# BOT-CPU.net
KiCad netlist of a schematic drawn in Altium Designer
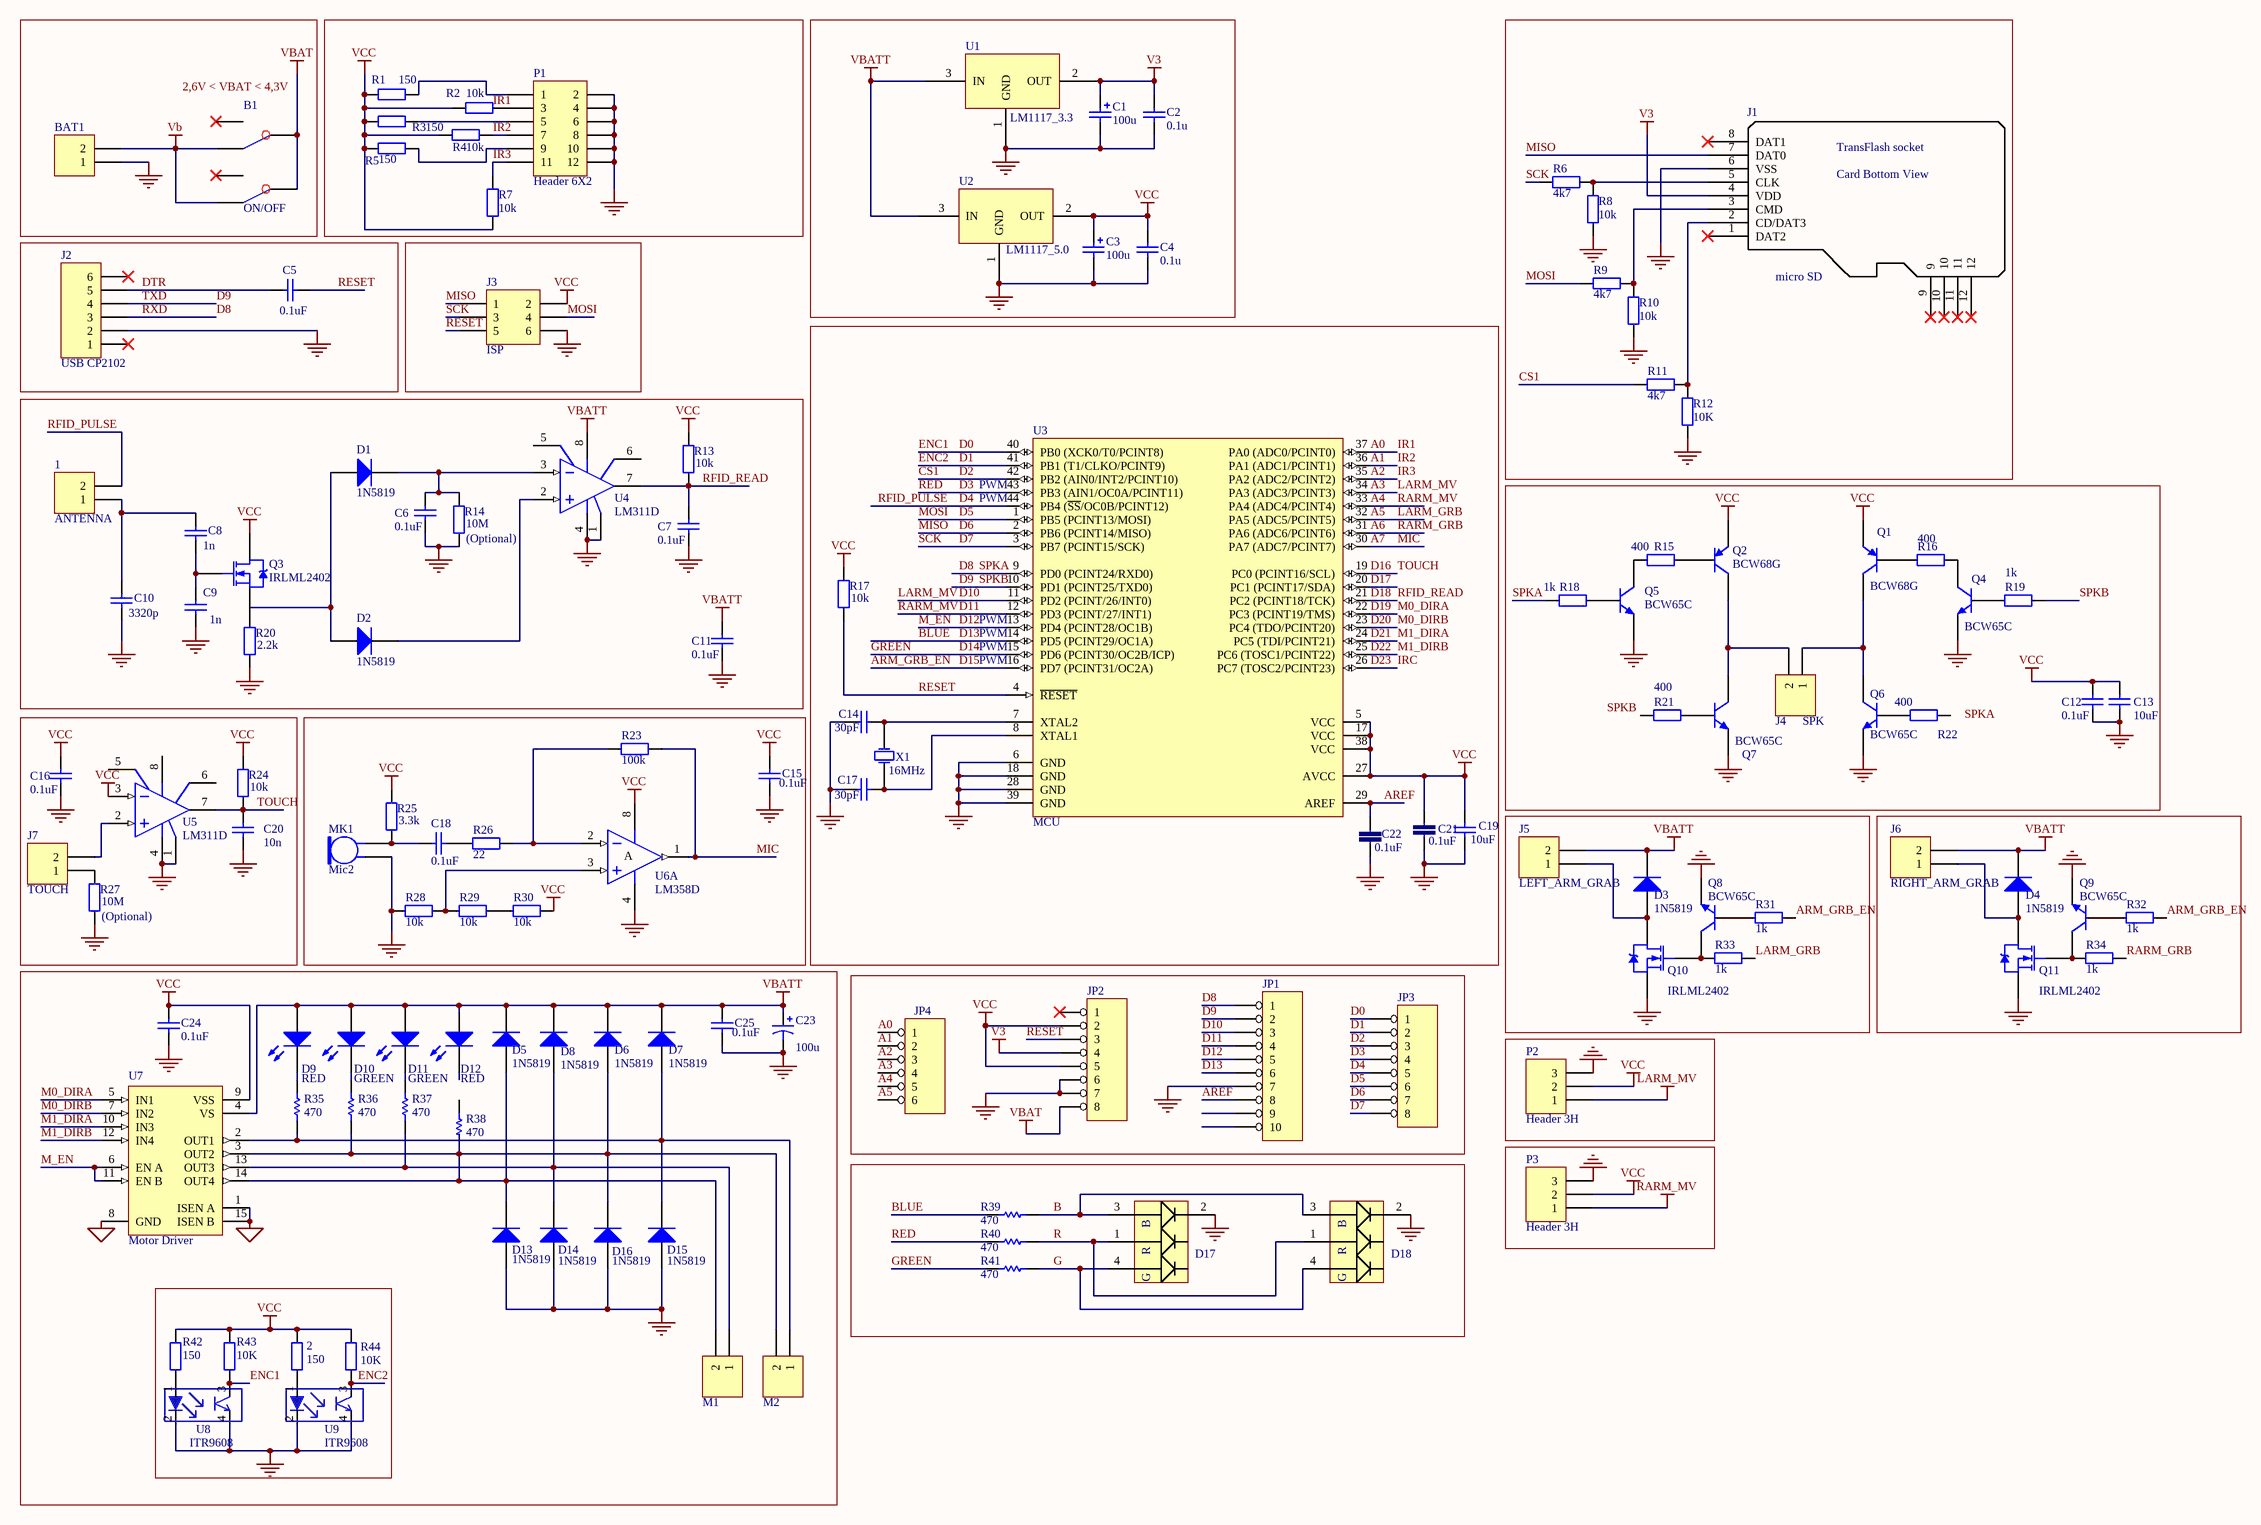
[diagram p0: BOT-CPU.SchDoc]

(export (version "E")
  (design (tool "Eeschema 10.0.6"))
  (components
    (comp (ref "1")
      (value "ANTENNA")
      (footprint "HDR1X2")
      (description "Header, 2-Pin")
      (fields (field (name "PUBLISHER") "Altium Limited"))
      (libsource (lib "") (part "Header 2_1"))
    )
    (comp (ref "2")
      (value "150")
      (footprint "0805")
      (description "Resistor")
      (fields (field (name "Comment") "1K") (field (name "PUBLISHER") "Altium Limited"))
      (libsource (lib "") (part "Res2_2"))
    )
    (comp (ref "B1") (value "ON/OFF") (footprint "KGPS22F03") (libsource (lib "*") (part "Component_1")))
    (comp (ref "BAT1")
      (value "Header 2")
      (footprint "CP2D2.54")
      (description "Header, 2-Pin")
      (fields (field (name "PUBLISHER") "Altium Limited"))
      (libsource (lib "") (part "Header 2_1"))
    )
    (comp (ref "C1")
      (value "100u")
      (footprint "C(D6.3*7)")
      (description "Polarized Capacitor (Axial)")
      (fields (field (name "ALTIUM_UNNAMED_1") "100u") (field (name "PUBLISHER") "Altium Limited"))
      (libsource (lib "*") (part "Cap Pol2"))
    )
    (comp (ref "C2")
      (value "0.1u")
      (footprint "0805")
      (description "Capacitor")
      (fields (field (name "PUBLISHER") "Altium Limited"))
      (libsource (lib "*") (part "Cap"))
    )
    (comp (ref "C3")
      (value "100u")
      (footprint "C(D6.3*7)")
      (description "Polarized Capacitor (Axial)")
      (fields (field (name "ALTIUM_UNNAMED_1") "100u") (field (name "PUBLISHER") "Altium Limited"))
      (libsource (lib "*") (part "Cap Pol2"))
    )
    (comp (ref "C4")
      (value "0.1u")
      (footprint "0805")
      (description "Capacitor")
      (fields (field (name "PUBLISHER") "Altium Limited"))
      (libsource (lib "*") (part "Cap"))
    )
    (comp (ref "C5")
      (value "0.1uF")
      (footprint "0805")
      (description "Capacitor")
      (fields (field (name "PUBLISHER") "*"))
      (libsource (lib "*") (part "Cap"))
    )
    (comp (ref "C6")
      (value "0.1uF")
      (footprint "0805")
      (description "Capacitor")
      (fields (field (name "PUBLISHER") "Altium Limited"))
      (libsource (lib "*") (part "Cap"))
    )
    (comp (ref "C7")
      (value "0.1uF")
      (footprint "0805")
      (description "Capacitor")
      (fields (field (name "PUBLISHER") "Altium Limited"))
      (libsource (lib "*") (part "Cap"))
    )
    (comp (ref "C8")
      (value "1n")
      (footprint "0805")
      (description "Capacitor")
      (fields (field (name "Comment") "1nF") (field (name "PUBLISHER") "Altium Limited"))
      (libsource (lib "*") (part "Cap"))
    )
    (comp (ref "C9")
      (value "1n")
      (footprint "0805")
      (description "Capacitor")
      (fields (field (name "Comment") "1nF") (field (name "PUBLISHER") "Altium Limited"))
      (libsource (lib "*") (part "Cap"))
    )
    (comp (ref "C10")
      (value "3320p")
      (footprint "0805")
      (description "Capacitor")
      (fields (field (name "Comment") "3320pF") (field (name "PUBLISHER") "Altium Limited"))
      (libsource (lib "*") (part "Cap"))
    )
    (comp (ref "C11")
      (value "0.1uF")
      (footprint "0805")
      (description "Capacitor")
      (fields (field (name "PUBLISHER") "Altium Limited"))
      (libsource (lib "*") (part "Cap"))
    )
    (comp (ref "C12")
      (value "0.1uF")
      (footprint "0805")
      (description "Capacitor")
      (fields (field (name "PUBLISHER") "Altium Limited"))
      (libsource (lib "*") (part "Cap"))
    )
    (comp (ref "C13")
      (value "10uF")
      (footprint "1206")
      (description "Capacitor")
      (fields (field (name "PUBLISHER") "Altium Limited"))
      (libsource (lib "*") (part "Cap"))
    )
    (comp (ref "C14")
      (value "30pF")
      (footprint "0805")
      (description "Capacitor")
      (fields (field (name "PUBLISHER") "Altium Limited"))
      (libsource (lib "*") (part "Cap"))
    )
    (comp (ref "C15")
      (value "0.1uF")
      (footprint "0805")
      (description "Capacitor")
      (fields (field (name "PUBLISHER") "Altium Limited"))
      (libsource (lib "*") (part "Cap"))
    )
    (comp (ref "C16")
      (value "0.1uF")
      (footprint "0805")
      (description "Capacitor")
      (fields (field (name "PUBLISHER") "Altium Limited"))
      (libsource (lib "*") (part "Cap"))
    )
    (comp (ref "C17")
      (value "30pF")
      (footprint "0805")
      (description "Capacitor")
      (fields (field (name "PUBLISHER") "Altium Limited"))
      (libsource (lib "*") (part "Cap"))
    )
    (comp (ref "C18")
      (value "0.1uF")
      (footprint "0805")
      (description "Capacitor")
      (fields (field (name "PUBLISHER") "Altium Limited"))
      (libsource (lib "") (part "Cap_1"))
    )
    (comp (ref "C19")
      (value "10uF")
      (footprint "1206")
      (description "Capacitor")
      (fields (field (name "PUBLISHER") "Altium Limited"))
      (libsource (lib "*") (part "Cap"))
    )
    (comp (ref "C20")
      (value "10n")
      (footprint "0805")
      (description "Capacitor")
      (fields (field (name "Comment") "0.1uF") (field (name "PUBLISHER") "Altium Limited"))
      (libsource (lib "*") (part "Cap"))
    )
    (comp (ref "C21") (value "0.1uF") (footprint "0805") (libsource (lib "*") (part "CAP0402")))
    (comp (ref "C22") (value "0.1uF") (footprint "0805") (libsource (lib "") (part "CAP0402_1")))
    (comp (ref "C23")
      (value "100u")
      (footprint "C(D6.3*7)")
      (description "Polarized Capacitor (Radial)")
      (fields (field (name "Comment") "220u") (field (name "PUBLISHER") "Altium Limited"))
      (libsource (lib "*") (part "Cap Pol1"))
    )
    (comp (ref "C24")
      (value "0.1uF")
      (footprint "0805")
      (description "Capacitor")
      (fields (field (name "PUBLISHER") "Altium Limited"))
      (libsource (lib "*") (part "Cap"))
    )
    (comp (ref "C25")
      (value "0.1uF")
      (footprint "0805")
      (description "Capacitor")
      (fields (field (name "PUBLISHER") "Altium Limited"))
      (libsource (lib "*") (part "Cap"))
    )
    (comp (ref "D1")
      (value "1N5819")
      (footprint "4007-smt")
      (description "Default Diode")
      (fields (field (name "PUBLISHER") "Altium Limited"))
      (libsource (lib "*") (part "Diode"))
    )
    (comp (ref "D2")
      (value "1N5819")
      (footprint "4007-smt")
      (description "Default Diode")
      (fields (field (name "PUBLISHER") "Altium Limited"))
      (libsource (lib "*") (part "Diode"))
    )
    (comp (ref "D3")
      (value "1N5819")
      (footprint "4007-smt")
      (description "Default Diode")
      (fields (field (name "PUBLISHER") "Altium Limited"))
      (libsource (lib "*") (part "Diode"))
    )
    (comp (ref "D4")
      (value "1N5819")
      (footprint "4007-smt")
      (description "Default Diode")
      (fields (field (name "PUBLISHER") "Altium Limited"))
      (libsource (lib "*") (part "Diode"))
    )
    (comp (ref "D5")
      (value "1N5819")
      (footprint "4007-smt")
      (description "Default Diode")
      (fields (field (name "PUBLISHER") "Altium Limited"))
      (libsource (lib "*") (part "Diode"))
    )
    (comp (ref "D6")
      (value "1N5819")
      (footprint "4007-smt")
      (description "Default Diode")
      (fields (field (name "PUBLISHER") "Altium Limited"))
      (libsource (lib "*") (part "Diode"))
    )
    (comp (ref "D7")
      (value "1N5819")
      (footprint "4007-smt")
      (description "Default Diode")
      (fields (field (name "PUBLISHER") "Altium Limited"))
      (libsource (lib "*") (part "Diode"))
    )
    (comp (ref "D8")
      (value "1N5819")
      (footprint "4007-smt")
      (description "Default Diode")
      (fields (field (name "PUBLISHER") "*"))
      (libsource (lib "*") (part "Diode"))
    )
    (comp (ref "D9")
      (value "RED")
      (footprint "LED-SMT")
      (description "Typical INFRARED GaAs LED")
      (fields (field (name "PUBLISHER") "Altium Limited"))
      (libsource (lib "*") (part "LED0"))
    )
    (comp (ref "D10")
      (value "GREEN")
      (footprint "LED-SMT")
      (description "Typical INFRARED GaAs LED")
      (fields (field (name "PUBLISHER") "Altium Limited"))
      (libsource (lib "*") (part "LED0"))
    )
    (comp (ref "D11")
      (value "GREEN")
      (footprint "LED-SMT")
      (description "Typical INFRARED GaAs LED")
      (fields (field (name "PUBLISHER") "Altium Limited"))
      (libsource (lib "*") (part "LED0"))
    )
    (comp (ref "D12")
      (value "RED")
      (footprint "LED-SMT")
      (description "Typical INFRARED GaAs LED")
      (fields (field (name "PUBLISHER") "Altium Limited"))
      (libsource (lib "*") (part "LED0"))
    )
    (comp (ref "D13")
      (value "1N5819")
      (footprint "4007-smt")
      (description "Default Diode")
      (fields (field (name "PUBLISHER") "Altium Limited"))
      (libsource (lib "*") (part "Diode"))
    )
    (comp (ref "D14")
      (value "1N5819")
      (footprint "4007-smt")
      (description "Default Diode")
      (fields (field (name "PUBLISHER") "Altium Limited"))
      (libsource (lib "*") (part "Diode"))
    )
    (comp (ref "D15")
      (value "1N5819")
      (footprint "4007-smt")
      (description "Default Diode")
      (fields (field (name "PUBLISHER") "Altium Limited"))
      (libsource (lib "*") (part "Diode"))
    )
    (comp (ref "D16")
      (value "1N5819")
      (footprint "4007-smt")
      (description "Default Diode")
      (fields (field (name "PUBLISHER") "Altium Limited"))
      (libsource (lib "*") (part "Diode"))
    )
    (comp (ref "D17") (value "RGB 5mm") (footprint "LED_RGB") (libsource (lib "*") (part "RGB PTH")))
    (comp (ref "D18") (value "RGB 5mm") (footprint "LED_RGB") (libsource (lib "*") (part "RGB PTH")))
    (comp (ref "J1")
      (value "micro SD")
      (footprint "MICRO_SD")
      (description "Transflash Socket")
      (libsource (lib "*") (part "JJ TRANSFLASH"))
    )
    (comp (ref "J2")
      (value "USB CP2102")
      (footprint "SIP6")
      (description "Header, 6-Pin")
      (fields (field (name "PUBLISHER") "Altium Limited"))
      (libsource (lib "*") (part "Header 6"))
    )
    (comp (ref "J3")
      (value "ISP")
      (footprint "con-6")
      (description "Header, 3-Pin, Dual row")
      (fields (field (name "PUBLISHER") "Altium Limited"))
      (libsource (lib "*") (part "Header 3X2"))
    )
    (comp (ref "J4")
      (value "SPK")
      (footprint "sip2")
      (description "Header, 2-Pin")
      (fields (field (name "PUBLISHER") "Altium Limited"))
      (libsource (lib "*") (part "Header 2"))
    )
    (comp (ref "J5")
      (value "LEFT_ARM_GRAB")
      (footprint "HDR1X2")
      (description "Header, 2-Pin")
      (fields (field (name "PUBLISHER") "Altium Limited"))
      (libsource (lib "") (part "Header 2_1"))
    )
    (comp (ref "J6")
      (value "RIGHT_ARM_GRAB")
      (footprint "HDR1X2")
      (description "Header, 2-Pin")
      (fields (field (name "PUBLISHER") "Altium Limited"))
      (libsource (lib "") (part "Header 2_1"))
    )
    (comp (ref "J7")
      (value "TOUCH")
      (footprint "HDR1X2")
      (description "Header, 2-Pin")
      (fields (field (name "PUBLISHER") "Altium Limited"))
      (libsource (lib "") (part "Header 2_1"))
    )
    (comp (ref "JP1") (value "PADS") (footprint "ARDUINO_10*1") (libsource (lib "*") (part "HEADER 10")))
    (comp (ref "JP2")
      (value "PADS")
      (footprint "ARDUINO_8*1")
      (description "8 Pin Header")
      (libsource (lib "*") (part "8 HEADER"))
    )
    (comp (ref "JP3")
      (value "PADS")
      (footprint "ARDUINO_8*1")
      (description "8 Pin Header")
      (libsource (lib "*") (part "8 HEADER"))
    )
    (comp (ref "JP4") (value "PADS") (footprint "ARDUINO_6*1") (libsource (lib "*") (part "HEADER 6")))
    (comp (ref "M1")
      (value "MOLEX")
      (footprint "CP2D2.54")
      (description "Header, 2-Pin")
      (fields (field (name "PUBLISHER") "Altium Limited"))
      (libsource (lib "*") (part "Header 2"))
    )
    (comp (ref "M2")
      (value "MOLEX")
      (footprint "CP2D2.54")
      (description "Header, 2-Pin")
      (fields (field (name "PUBLISHER") "Altium Limited"))
      (libsource (lib "*") (part "Header 2"))
    )
    (comp (ref "MK1")
      (value "Mic2")
      (footprint "MIC")
      (description "Microphone")
      (fields (field (name "PUBLISHER") "*"))
      (libsource (lib "*") (part "Mic2"))
    )
    (comp (ref "P1")
      (value "Header 6X2")
      (footprint "HDR2X6")
      (description "Header, 6-Pin, Dual row")
      (fields (field (name "PUBLISHER") "Altium Limited"))
      (libsource (lib "Miscellaneous Connectors") (part "Header 6X2"))
    )
    (comp (ref "P2")
      (value "Header 3H")
      (footprint "HDR1X3H")
      (description "Header, 3-Pin, Right Angle")
      (fields (field (name "PUBLISHER") "Altium Limited"))
      (libsource (lib "Miscellaneous Connectors") (part "Header 3H"))
    )
    (comp (ref "P3")
      (value "Header 3H")
      (footprint "HDR1X3H")
      (description "Header, 3-Pin, Right Angle")
      (fields (field (name "PUBLISHER") "Altium Limited"))
      (libsource (lib "Miscellaneous Connectors") (part "Header 3H"))
    )
    (comp (ref "Q1")
      (value "BCW68G")
      (footprint "SOT-23A_N")
      (description "PNP General Purpose Amplifier")
      (fields (field (name "PUBLISHER") "Altium Limited"))
      (libsource (lib "FSC Discrete BJT") (part "BCW68G"))
    )
    (comp (ref "Q2")
      (value "BCW68G")
      (footprint "SOT-23A_N")
      (description "PNP General Purpose Amplifier")
      (fields (field (name "PUBLISHER") "Altium Limited"))
      (libsource (lib "FSC Discrete BJT") (part "BCW68G"))
    )
    (comp (ref "Q3")
      (value "IRLML2402")
      (footprint "SOT-23_N")
      (description "HEXFET Power MOSFET")
      (fields (field (name "PUBLISHER") "Altium Limited"))
      (libsource (lib "IR Discrete MOSFET - Power") (part "IRLML2402"))
    )
    (comp (ref "Q4")
      (value "BCW65C")
      (footprint "SOT-23A_N")
      (description "NPN General Purpose Amplifier")
      (fields (field (name "PUBLISHER") "Altium Limited"))
      (libsource (lib "FSC Discrete BJT") (part "BCW65C"))
    )
    (comp (ref "Q5")
      (value "BCW65C")
      (footprint "SOT-23A_N")
      (description "NPN General Purpose Amplifier")
      (fields (field (name "PUBLISHER") "Altium Limited"))
      (libsource (lib "FSC Discrete BJT") (part "BCW65C"))
    )
    (comp (ref "Q6")
      (value "BCW65C")
      (footprint "SOT-23A_N")
      (description "NPN General Purpose Amplifier")
      (fields (field (name "PUBLISHER") "Altium Limited"))
      (libsource (lib "FSC Discrete BJT") (part "BCW65C"))
    )
    (comp (ref "Q7")
      (value "BCW65C")
      (footprint "SOT-23A_N")
      (description "NPN General Purpose Amplifier")
      (fields (field (name "PUBLISHER") "Altium Limited"))
      (libsource (lib "FSC Discrete BJT") (part "BCW65C"))
    )
    (comp (ref "Q8")
      (value "BCW65C")
      (footprint "SOT-23A_N")
      (description "NPN General Purpose Amplifier")
      (fields (field (name "PUBLISHER") "Altium Limited"))
      (libsource (lib "FSC Discrete BJT") (part "BCW65C"))
    )
    (comp (ref "Q9")
      (value "BCW65C")
      (footprint "SOT-23A_N")
      (description "NPN General Purpose Amplifier")
      (fields (field (name "PUBLISHER") "Altium Limited"))
      (libsource (lib "FSC Discrete BJT") (part "BCW65C"))
    )
    (comp (ref "Q10")
      (value "IRLML2402")
      (footprint "SOT-23_N")
      (description "HEXFET Power MOSFET")
      (fields (field (name "PUBLISHER") "Altium Limited"))
      (libsource (lib "IR Discrete MOSFET - Power") (part "IRLML2402"))
    )
    (comp (ref "Q11")
      (value "IRLML2402")
      (footprint "SOT-23_N")
      (description "HEXFET Power MOSFET")
      (fields (field (name "PUBLISHER") "Altium Limited"))
      (libsource (lib "IR Discrete MOSFET - Power") (part "IRLML2402"))
    )
    (comp (ref "R1")
      (value "150")
      (footprint "0805")
      (description "Resistor")
      (fields (field (name "PUBLISHER") "Altium Limited"))
      (libsource (lib "*") (part "Res2"))
    )
    (comp (ref "R2")
      (value "10k")
      (footprint "0805")
      (description "Resistor")
      (fields (field (name "PUBLISHER") "Altium Limited"))
      (libsource (lib "*") (part "Res2"))
    )
    (comp (ref "R3")
      (value "150")
      (footprint "0805")
      (description "Resistor")
      (fields (field (name "PUBLISHER") "Altium Limited"))
      (libsource (lib "*") (part "Res2"))
    )
    (comp (ref "R4")
      (value "10k")
      (footprint "0805")
      (description "Resistor")
      (fields (field (name "PUBLISHER") "Altium Limited"))
      (libsource (lib "*") (part "Res2"))
    )
    (comp (ref "R5")
      (value "150")
      (footprint "0805")
      (description "Resistor")
      (fields (field (name "PUBLISHER") "Altium Limited"))
      (libsource (lib "*") (part "Res2"))
    )
    (comp (ref "R6")
      (value "4k7")
      (footprint "0805")
      (description "Resistor")
      (fields (field (name "PUBLISHER") "Altium Limited"))
      (libsource (lib "") (part "Res2_1"))
    )
    (comp (ref "R7")
      (value "10k")
      (footprint "0805")
      (description "Resistor")
      (fields (field (name "PUBLISHER") "Altium Limited"))
      (libsource (lib "") (part "Res2_2"))
    )
    (comp (ref "R8")
      (value "10k")
      (footprint "0805")
      (description "Resistor")
      (fields (field (name "PUBLISHER") "Altium Limited"))
      (libsource (lib "") (part "Res2_3"))
    )
    (comp (ref "R9")
      (value "4k7")
      (footprint "0805")
      (description "Resistor")
      (fields (field (name "Comment") "10k") (field (name "PUBLISHER") "Altium Limited"))
      (libsource (lib "") (part "Res2_1"))
    )
    (comp (ref "R10")
      (value "10k")
      (footprint "0805")
      (description "Resistor")
      (fields (field (name "Comment") "20K") (field (name "PUBLISHER") "Altium Limited"))
      (libsource (lib "") (part "Res2_3"))
    )
    (comp (ref "R11")
      (value "4k7")
      (footprint "0805")
      (description "Resistor")
      (fields (field (name "Comment") "10k") (field (name "PUBLISHER") "Altium Limited"))
      (libsource (lib "") (part "Res2_3"))
    )
    (comp (ref "R12")
      (value "10K")
      (footprint "0805")
      (description "Resistor")
      (fields (field (name "PUBLISHER") "Altium Limited"))
      (libsource (lib "") (part "Res2_1"))
    )
    (comp (ref "R13")
      (value "10k")
      (footprint "0805")
      (description "Resistor")
      (fields (field (name "PUBLISHER") "Altium Limited"))
      (libsource (lib "") (part "Res2_1"))
    )
    (comp (ref "R14")
      (value "(Optional)")
      (footprint "0805")
      (description "Resistor")
      (fields (field (name "ALTIUM_VALUE") "10M") (field (name "PUBLISHER") "Altium Limited"))
      (libsource (lib "") (part "Res2_1"))
    )
    (comp (ref "R15")
      (value "400")
      (footprint "0805")
      (description "Resistor")
      (fields (field (name "PUBLISHER") "Altium Limited"))
      (libsource (lib "*") (part "Res2"))
    )
    (comp (ref "R16")
      (value "400")
      (footprint "0805")
      (description "Resistor")
      (fields (field (name "PUBLISHER") "Altium Limited"))
      (libsource (lib "") (part "Res2_1"))
    )
    (comp (ref "R17")
      (value "10k")
      (footprint "0805")
      (description "Resistor")
      (fields (field (name "Comment") "2.2k") (field (name "PUBLISHER") "Altium Limited"))
      (libsource (lib "") (part "Res2_1"))
    )
    (comp (ref "R18")
      (value "1k")
      (footprint "0805")
      (description "Resistor")
      (fields (field (name "Comment") "1K") (field (name "PUBLISHER") "Altium Limited"))
      (libsource (lib "*") (part "Res2"))
    )
    (comp (ref "R19")
      (value "1k")
      (footprint "0805")
      (description "Resistor")
      (fields (field (name "Comment") "1K") (field (name "PUBLISHER") "Altium Limited"))
      (libsource (lib "") (part "Res2_1"))
    )
    (comp (ref "R20")
      (value "2.2k")
      (footprint "0805")
      (description "Resistor")
      (fields (field (name "PUBLISHER") "Altium Limited"))
      (libsource (lib "") (part "Res2_1"))
    )
    (comp (ref "R21")
      (value "400")
      (footprint "0805")
      (description "Resistor")
      (fields (field (name "PUBLISHER") "Altium Limited"))
      (libsource (lib "*") (part "Res2"))
    )
    (comp (ref "R22")
      (value "400")
      (footprint "0805")
      (description "Resistor")
      (fields (field (name "PUBLISHER") "Altium Limited"))
      (libsource (lib "") (part "Res2_1"))
    )
    (comp (ref "R23")
      (value "100k")
      (footprint "0805")
      (description "Resistor")
      (fields (field (name "Comment") "1M") (field (name "PUBLISHER") "Altium Limited"))
      (libsource (lib "*") (part "Res2"))
    )
    (comp (ref "R24")
      (value "10k")
      (footprint "0805")
      (description "Resistor")
      (fields (field (name "PUBLISHER") "Altium Limited"))
      (libsource (lib "") (part "Res2_1"))
    )
    (comp (ref "R25")
      (value "3.3k")
      (footprint "0805")
      (description "Resistor")
      (fields (field (name "PUBLISHER") "Altium Limited"))
      (libsource (lib "") (part "Res2_1"))
    )
    (comp (ref "R26")
      (value "22")
      (footprint "0805")
      (description "Resistor")
      (fields (field (name "PUBLISHER") "Altium Limited"))
      (libsource (lib "*") (part "Res2"))
    )
    (comp (ref "R27")
      (value "(Optional)")
      (footprint "0805")
      (description "Resistor")
      (fields (field (name "ALTIUM_VALUE") "10M") (field (name "PUBLISHER") "Altium Limited"))
      (libsource (lib "") (part "Res2_1"))
    )
    (comp (ref "R28")
      (value "10k")
      (footprint "0805")
      (description "Resistor")
      (fields (field (name "PUBLISHER") "Altium Limited"))
      (libsource (lib "*") (part "Res2"))
    )
    (comp (ref "R29")
      (value "10k")
      (footprint "0805")
      (description "Resistor")
      (fields (field (name "PUBLISHER") "Altium Limited"))
      (libsource (lib "*") (part "Res2"))
    )
    (comp (ref "R30")
      (value "10k")
      (footprint "0805")
      (description "Resistor")
      (fields (field (name "PUBLISHER") "Altium Limited"))
      (libsource (lib "*") (part "Res2"))
    )
    (comp (ref "R31")
      (value "1k")
      (footprint "0805")
      (description "Resistor")
      (fields (field (name "Comment") "2.2k") (field (name "PUBLISHER") "Altium Limited"))
      (libsource (lib "*") (part "Res2"))
    )
    (comp (ref "R32")
      (value "1k")
      (footprint "0805")
      (description "Resistor")
      (fields (field (name "Comment") "2.2k") (field (name "PUBLISHER") "Altium Limited"))
      (libsource (lib "*") (part "Res2"))
    )
    (comp (ref "R33")
      (value "1k")
      (footprint "0805")
      (description "Resistor")
      (fields (field (name "Comment") "2.2k") (field (name "PUBLISHER") "Altium Limited"))
      (libsource (lib "*") (part "Res2"))
    )
    (comp (ref "R34")
      (value "1k")
      (footprint "0805")
      (description "Resistor")
      (fields (field (name "Comment") "2.2k") (field (name "PUBLISHER") "Altium Limited"))
      (libsource (lib "*") (part "Res2"))
    )
    (comp (ref "R35")
      (value "470")
      (footprint "0805")
      (description "Resistor")
      (fields (field (name "PUBLISHER") "Altium Limited"))
      (libsource (lib "*") (part "Res1"))
    )
    (comp (ref "R36")
      (value "470")
      (footprint "0805")
      (description "Resistor")
      (fields (field (name "PUBLISHER") "Altium Limited"))
      (libsource (lib "*") (part "Res1"))
    )
    (comp (ref "R37")
      (value "470")
      (footprint "0805")
      (description "Resistor")
      (fields (field (name "PUBLISHER") "Altium Limited"))
      (libsource (lib "*") (part "Res1"))
    )
    (comp (ref "R38")
      (value "470")
      (footprint "0805")
      (description "Resistor")
      (fields (field (name "PUBLISHER") "Altium Limited"))
      (libsource (lib "*") (part "Res1"))
    )
    (comp (ref "R39")
      (value "470")
      (footprint "0805")
      (description "Resistor")
      (fields (field (name "Comment") "560") (field (name "PUBLISHER") "Altium Limited"))
      (libsource (lib "*") (part "Res1"))
    )
    (comp (ref "R40")
      (value "470")
      (footprint "0805")
      (description "Resistor")
      (fields (field (name "PUBLISHER") "Altium Limited"))
      (libsource (lib "*") (part "Res1"))
    )
    (comp (ref "R41")
      (value "470")
      (footprint "0805")
      (description "Resistor")
      (fields (field (name "PUBLISHER") "Altium Limited"))
      (libsource (lib "*") (part "Res1"))
    )
    (comp (ref "R42")
      (value "150")
      (footprint "0805")
      (description "Resistor")
      (fields (field (name "Comment") "1K") (field (name "PUBLISHER") "Altium Limited"))
      (libsource (lib "") (part "Res2_2"))
    )
    (comp (ref "R43")
      (value "10K")
      (footprint "0805")
      (description "Resistor")
      (fields (field (name "Comment") "1K") (field (name "PUBLISHER") "Altium Limited"))
      (libsource (lib "") (part "Res2_2"))
    )
    (comp (ref "R44")
      (value "10K")
      (footprint "0805")
      (description "Resistor")
      (fields (field (name "Comment") "1K") (field (name "PUBLISHER") "Altium Limited"))
      (libsource (lib "") (part "Res2_2"))
    )
    (comp (ref "U1") (value "LM1117_3.3") (footprint "LM1117") (libsource (lib "*") (part "LM1117")))
    (comp (ref "U2") (value "LM1117_5.0") (footprint "LM1117") (libsource (lib "*") (part "LM1117")))
    (comp (ref "U3")
      (value "MCU")
      (footprint "QFP44")
      (description "8-bit AVR Microcontroller, 2.7-5.5V, 20MHz, 64KB Flash, 2KB EEPROM, 4KB SRAM, 44-pin TQFP")
      (libsource (lib "*") (part "ATmega644-20AU"))
    )
    (comp (ref "U4")
      (value "LM311D")
      (footprint "SO8_N")
      (description "Voltage Comparator")
      (fields (field (name "PUBLISHER") "Altium Limited"))
      (libsource (lib "ST Analog Comparator") (part "LM311D"))
    )
    (comp (ref "U5")
      (value "LM311D")
      (footprint "SO8_N")
      (description "Voltage Comparator")
      (fields (field (name "PUBLISHER") "Altium Limited"))
      (libsource (lib "ST Analog Comparator") (part "LM311D"))
    )
    (comp (ref "U6")
      (value "LM358D")
      (footprint "D008_L")
      (description "Dual Operational Amplifier")
      (fields (field (name "PUBLISHER") "Altium Limited"))
      (libsource (lib "TI Operational Amplifier") (part "LM358D"))
    )
    (comp (ref "U7")
      (value "Motor Driver")
      (footprint "L298N")
      (description "Dual Full Bridge Driver")
      (fields (field (name "PUBLISHER") "Altium Limited"))
      (libsource (lib "*") (part "L298N"))
    )
    (comp (ref "U8") (value "ITR9608") (footprint "ITR9608") (libsource (lib "*") (part "ITR9608")))
    (comp (ref "U9") (value "ITR9608") (footprint "ITR9608") (libsource (lib "*") (part "ITR9608")))
    (comp (ref "X1")
      (value "16MHz")
      (footprint "XTAL2")
      (description "Crystal Oscillator")
      (fields (field (name "PUBLISHER") "Altium Limited"))
      (libsource (lib "*") (part "XTAL"))
    )
  )
  (nets
    (net (code "1") (name "/A0") (class "Default")
      (node (ref "JP4") (pin "1") (pinfunction "1_1") (pintype "passive"))
      (node (ref "U3") (pin "37") (pinfunction "PA0_(ADC0/PCINT0)_37") (pintype "bidirectional"))
    )
    (net (code "2") (name "/A1") (class "Default")
      (node (ref "JP4") (pin "2") (pinfunction "2_2") (pintype "passive"))
      (node (ref "P1") (pin "7") (pinfunction "7_7") (pintype "passive"))
      (node (ref "R4") (pin "2") (pinfunction "2_2") (pintype "passive"))
      (node (ref "U3") (pin "36") (pinfunction "PA1_(ADC1/PCINT1)_36") (pintype "bidirectional"))
    )
    (net (code "3") (name "/A2") (class "Default")
      (node (ref "JP4") (pin "3") (pinfunction "3_3") (pintype "passive"))
      (node (ref "P1") (pin "11") (pinfunction "11_11") (pintype "passive"))
      (node (ref "R7") (pin "2") (pinfunction "2_2") (pintype "passive"))
      (node (ref "U3") (pin "35") (pinfunction "PA2_(ADC2/PCINT2)_35") (pintype "bidirectional"))
    )
    (net (code "4") (name "/A5") (class "Default")
      (node (ref "JP4") (pin "6") (pinfunction "6_6") (pintype "passive"))
      (node (ref "R33") (pin "2") (pinfunction "2_2") (pintype "passive"))
      (node (ref "U3") (pin "32") (pinfunction "PA5_(ADC5/PCINT5)_32") (pintype "bidirectional"))
    )
    (net (code "5") (name "/A6") (class "Default")
      (node (ref "R34") (pin "2") (pinfunction "2_2") (pintype "passive"))
      (node (ref "U3") (pin "31") (pinfunction "PA6_(ADC6/PCINT6)_31") (pintype "bidirectional"))
    )
    (net (code "6") (name "/A7") (class "Default")
      (node (ref "R23") (pin "2") (pinfunction "2_2") (pintype "passive"))
      (node (ref "U3") (pin "30") (pinfunction "PA7_(ADC7/PCINT7)_30") (pintype "bidirectional"))
      (node (ref "U6") (pin "1") (pinfunction "OUT_1") (pintype "output"))
    )
    (net (code "7") (name "/AREF") (class "Default")
      (node (ref "C22") (pin "2") (pinfunction "2_2") (pintype "passive"))
      (node (ref "JP1") (pin "8") (pinfunction "8_8") (pintype "passive"))
      (node (ref "U3") (pin "29") (pinfunction "AREF_29") (pintype "passive"))
    )
    (net (code "8") (name "/ARM_GRB_EN") (class "Default")
      (node (ref "R31") (pin "2") (pinfunction "2_2") (pintype "passive"))
      (node (ref "R32") (pin "2") (pinfunction "2_2") (pintype "passive"))
      (node (ref "U3") (pin "16") (pinfunction "PD7_(PCINT31/OC2A)_16") (pintype "bidirectional"))
    )
    (net (code "9") (name "/B") (class "Default")
      (node (ref "D17") (pin "3") (pinfunction "3_3") (pintype "passive"))
      (node (ref "D18") (pin "3") (pinfunction "3_3") (pintype "passive"))
      (node (ref "R39") (pin "2") (pinfunction "2_2") (pintype "passive"))
    )
    (net (code "10") (name "/BLUE") (class "Default")
      (node (ref "JP1") (pin "6") (pinfunction "6_6") (pintype "passive"))
      (node (ref "R39") (pin "1") (pinfunction "1_1") (pintype "passive"))
      (node (ref "U3") (pin "14") (pinfunction "PD5_(PCINT29/OC1A)_14") (pintype "bidirectional"))
    )
    (net (code "11") (name "/CS1") (class "Default")
      (node (ref "JP3") (pin "3") (pinfunction "3_3") (pintype "passive"))
      (node (ref "R11") (pin "2") (pinfunction "2_2") (pintype "passive"))
      (node (ref "U3") (pin "42") (pinfunction "PB2_(AIN0/INT2/PCINT10)_42") (pintype "bidirectional"))
    )
    (net (code "12") (name "/D0") (class "Default")
      (node (ref "JP3") (pin "1") (pinfunction "1_1") (pintype "passive"))
      (node (ref "R43") (pin "1") (pinfunction "1_1") (pintype "passive"))
      (node (ref "U3") (pin "40") (pinfunction "PB0_(XCK0/T0/PCINT8)_40") (pintype "bidirectional"))
      (node (ref "U8") (pin "3") (pinfunction "COLLECTOR_3") (pintype "passive"))
    )
    (net (code "13") (name "/D1") (class "Default")
      (node (ref "JP3") (pin "2") (pinfunction "2_2") (pintype "passive"))
      (node (ref "R44") (pin "1") (pinfunction "1_1") (pintype "passive"))
      (node (ref "U3") (pin "41") (pinfunction "PB1_(T1/CLKO/PCINT9)_41") (pintype "bidirectional"))
      (node (ref "U9") (pin "3") (pinfunction "COLLECTOR_3") (pintype "passive"))
    )
    (net (code "14") (name "/D3") (class "Default")
      (node (ref "JP3") (pin "4") (pinfunction "4_4") (pintype "passive"))
      (node (ref "R40") (pin "1") (pinfunction "1_1") (pintype "passive"))
      (node (ref "U3") (pin "43") (pinfunction "PB3_(AIN1/OC0A/PCINT11)_43") (pintype "bidirectional"))
    )
    (net (code "15") (name "/D4") (class "Default")
      (node (ref "1") (pin "2") (pinfunction "2_2") (pintype "passive"))
      (node (ref "JP3") (pin "5") (pinfunction "5_5") (pintype "passive"))
      (node (ref "U3") (pin "44") (pinfunction "PB4_(~{SS}/OC0B/PCINT12)_44") (pintype "bidirectional"))
    )
    (net (code "16") (name "/D5") (class "Default")
      (node (ref "J3") (pin "4") (pinfunction "4_4") (pintype "passive"))
      (node (ref "JP3") (pin "6") (pinfunction "6_6") (pintype "passive"))
      (node (ref "R9") (pin "2") (pinfunction "2_2") (pintype "passive"))
      (node (ref "U3") (pin "1") (pinfunction "PB5_(PCINT13/MOSI)_1") (pintype "bidirectional"))
    )
    (net (code "17") (name "/D6") (class "Default")
      (node (ref "J1") (pin "7") (pinfunction "DAT0_7") (pintype "passive"))
      (node (ref "J3") (pin "1") (pinfunction "1_1") (pintype "passive"))
      (node (ref "JP3") (pin "7") (pinfunction "7_7") (pintype "passive"))
      (node (ref "U3") (pin "2") (pinfunction "PB6_(PCINT14/MISO)_2") (pintype "bidirectional"))
    )
    (net (code "18") (name "/D7") (class "Default")
      (node (ref "J3") (pin "3") (pinfunction "3_3") (pintype "passive"))
      (node (ref "JP3") (pin "8") (pinfunction "8_8") (pintype "passive"))
      (node (ref "R6") (pin "2") (pinfunction "2_2") (pintype "passive"))
      (node (ref "U3") (pin "3") (pinfunction "PB7_(PCINT15/SCK)_3") (pintype "bidirectional"))
    )
    (net (code "19") (name "/D8") (class "Default")
      (node (ref "J2") (pin "3") (pinfunction "3_3") (pintype "passive"))
      (node (ref "JP1") (pin "1") (pinfunction "1_1") (pintype "passive"))
      (node (ref "R18") (pin "1") (pinfunction "1_1") (pintype "passive"))
      (node (ref "U3") (pin "9") (pinfunction "PD0_(PCINT24/RXD0)_9") (pintype "bidirectional"))
    )
    (net (code "20") (name "/D9") (class "Default")
      (node (ref "J2") (pin "4") (pinfunction "4_4") (pintype "passive"))
      (node (ref "JP1") (pin "2") (pinfunction "2_2") (pintype "passive"))
      (node (ref "R19") (pin "1") (pinfunction "1_1") (pintype "passive"))
      (node (ref "U3") (pin "10") (pinfunction "PD1_(PCINT25/TXD0)_10") (pintype "bidirectional"))
    )
    (net (code "21") (name "/D12") (class "Default")
      (node (ref "JP1") (pin "5") (pinfunction "5_5") (pintype "passive"))
      (node (ref "U3") (pin "13") (pinfunction "PD4_(PCINT28/OC1B)_13") (pintype "bidirectional"))
      (node (ref "U7") (pin "11") (pinfunction "EN_B_11") (pintype "input"))
      (node (ref "U7") (pin "6") (pinfunction "EN_A_6") (pintype "input"))
    )
    (net (code "22") (name "/D14") (class "Default")
      (node (ref "R41") (pin "1") (pinfunction "1_1") (pintype "passive"))
      (node (ref "U3") (pin "15") (pinfunction "PD6_(PCINT30/OC2B/ICP)_15") (pintype "bidirectional"))
    )
    (net (code "23") (name "/D16") (class "Default")
      (node (ref "C20") (pin "2") (pinfunction "2_2") (pintype "passive"))
      (node (ref "R24") (pin "2") (pinfunction "2_2") (pintype "passive"))
      (node (ref "U3") (pin "19") (pinfunction "PC0_(PCINT16/SCL)_19") (pintype "bidirectional"))
      (node (ref "U5") (pin "7") (pinfunction "OUT_7") (pintype "open_collector"))
    )
    (net (code "24") (name "/D17") (class "Default")
      (node (ref "U3") (pin "20") (pinfunction "PC1_(PCINT17/SDA)_20") (pintype "bidirectional"))
    )
    (net (code "25") (name "/D18") (class "Default")
      (node (ref "C7") (pin "2") (pinfunction "2_2") (pintype "passive"))
      (node (ref "R13") (pin "2") (pinfunction "2_2") (pintype "passive"))
      (node (ref "U3") (pin "21") (pinfunction "PC2_(PCINT18/TCK)_21") (pintype "bidirectional"))
      (node (ref "U4") (pin "7") (pinfunction "OUT_7") (pintype "open_collector"))
    )
    (net (code "26") (name "/D19") (class "Default")
      (node (ref "U3") (pin "22") (pinfunction "PC3_(PCINT19/TMS)_22") (pintype "bidirectional"))
      (node (ref "U7") (pin "5") (pinfunction "IN1_5") (pintype "input"))
    )
    (net (code "27") (name "/D20") (class "Default")
      (node (ref "U3") (pin "23") (pinfunction "PC4_(TDO/PCINT20)_23") (pintype "bidirectional"))
      (node (ref "U7") (pin "7") (pinfunction "IN2_7") (pintype "input"))
    )
    (net (code "28") (name "/D21") (class "Default")
      (node (ref "U3") (pin "24") (pinfunction "PC5_(TDI/PCINT21)_24") (pintype "bidirectional"))
      (node (ref "U7") (pin "10") (pinfunction "IN3_10") (pintype "input"))
    )
    (net (code "29") (name "/D22") (class "Default")
      (node (ref "U3") (pin "25") (pinfunction "PC6_(TOSC1/PCINT22)_25") (pintype "bidirectional"))
      (node (ref "U7") (pin "12") (pinfunction "IN4_12") (pintype "input"))
    )
    (net (code "30") (name "/D23") (class "Default")
      (node (ref "U3") (pin "26") (pinfunction "PC7_(TOSC2/PCINT23)_26") (pintype "bidirectional"))
    )
    (net (code "31") (name "/DTR") (class "Default")
      (node (ref "C5") (pin "1") (pinfunction "1_1") (pintype "passive"))
      (node (ref "J2") (pin "5") (pinfunction "5_5") (pintype "passive"))
    )
    (net (code "32") (name "/G") (class "Default")
      (node (ref "D17") (pin "4") (pinfunction "4_4") (pintype "passive"))
      (node (ref "D18") (pin "4") (pinfunction "4_4") (pintype "passive"))
      (node (ref "R41") (pin "2") (pinfunction "2_2") (pintype "passive"))
    )
    (net (code "33") (name "/R") (class "Default")
      (node (ref "D17") (pin "1") (pinfunction "1_1") (pintype "passive"))
      (node (ref "D18") (pin "1") (pinfunction "1_1") (pintype "passive"))
      (node (ref "R40") (pin "2") (pinfunction "2_2") (pintype "passive"))
    )
    (net (code "34") (name "/RESET") (class "Default")
      (node (ref "C5") (pin "2") (pinfunction "2_2") (pintype "passive"))
      (node (ref "J3") (pin "5") (pinfunction "5_5") (pintype "passive"))
      (node (ref "JP2") (pin "3") (pinfunction "3_3") (pintype "passive"))
      (node (ref "R17") (pin "2") (pinfunction "2_2") (pintype "passive"))
      (node (ref "U3") (pin "4") (pinfunction "~{RESET}_4") (pintype "input"))
    )
    (net (code "35") (name "GND") (class "Default")
      (node (ref "BAT1") (pin "1") (pinfunction "1_1") (pintype "passive"))
      (node (ref "C1") (pin "2") (pinfunction "2_2") (pintype "passive"))
      (node (ref "C10") (pin "1") (pinfunction "1_1") (pintype "passive"))
      (node (ref "C11") (pin "1") (pinfunction "1_1") (pintype "passive"))
      (node (ref "C12") (pin "1") (pinfunction "1_1") (pintype "passive"))
      (node (ref "C13") (pin "1") (pinfunction "1_1") (pintype "passive"))
      (node (ref "C14") (pin "1") (pinfunction "1_1") (pintype "passive"))
      (node (ref "C15") (pin "2") (pinfunction "2_2") (pintype "passive"))
      (node (ref "C16") (pin "1") (pinfunction "1_1") (pintype "passive"))
      (node (ref "C17") (pin "1") (pinfunction "1_1") (pintype "passive"))
      (node (ref "C19") (pin "1") (pinfunction "1_1") (pintype "passive"))
      (node (ref "C2") (pin "1") (pinfunction "1_1") (pintype "passive"))
      (node (ref "C20") (pin "1") (pinfunction "1_1") (pintype "passive"))
      (node (ref "C21") (pin "1") (pinfunction "1_1") (pintype "passive"))
      (node (ref "C22") (pin "1") (pinfunction "1_1") (pintype "passive"))
      (node (ref "C23") (pin "2") (pinfunction "2_2") (pintype "passive"))
      (node (ref "C24") (pin "2") (pinfunction "2_2") (pintype "passive"))
      (node (ref "C25") (pin "2") (pinfunction "2_2") (pintype "passive"))
      (node (ref "C3") (pin "2") (pinfunction "2_2") (pintype "passive"))
      (node (ref "C4") (pin "1") (pinfunction "1_1") (pintype "passive"))
      (node (ref "C6") (pin "1") (pinfunction "1_1") (pintype "passive"))
      (node (ref "C7") (pin "1") (pinfunction "1_1") (pintype "passive"))
      (node (ref "C9") (pin "1") (pinfunction "1_1") (pintype "passive"))
      (node (ref "D13") (pin "1") (pinfunction "A_1") (pintype "passive"))
      (node (ref "D14") (pin "1") (pinfunction "A_1") (pintype "passive"))
      (node (ref "D15") (pin "1") (pinfunction "A_1") (pintype "passive"))
      (node (ref "D16") (pin "1") (pinfunction "A_1") (pintype "passive"))
      (node (ref "D17") (pin "2") (pinfunction "2_2") (pintype "passive"))
      (node (ref "D18") (pin "2") (pinfunction "2_2") (pintype "passive"))
      (node (ref "J1") (pin "6") (pinfunction "VSS_6") (pintype "passive"))
      (node (ref "J2") (pin "2") (pinfunction "2_2") (pintype "passive"))
      (node (ref "J3") (pin "6") (pinfunction "6_6") (pintype "passive"))
      (node (ref "JP1") (pin "7") (pinfunction "7_7") (pintype "passive"))
      (node (ref "JP2") (pin "6") (pinfunction "6_6") (pintype "passive"))
      (node (ref "JP2") (pin "7") (pinfunction "7_7") (pintype "passive"))
      (node (ref "MK1") (pin "2") (pinfunction "2_2") (pintype "passive"))
      (node (ref "P1") (pin "10") (pinfunction "10_10") (pintype "passive"))
      (node (ref "P1") (pin "12") (pinfunction "12_12") (pintype "passive"))
      (node (ref "P1") (pin "2") (pinfunction "2_2") (pintype "passive"))
      (node (ref "P1") (pin "4") (pinfunction "4_4") (pintype "passive"))
      (node (ref "P1") (pin "6") (pinfunction "6_6") (pintype "passive"))
      (node (ref "P1") (pin "8") (pinfunction "8_8") (pintype "passive"))
      (node (ref "P2") (pin "3") (pinfunction "3_3") (pintype "passive"))
      (node (ref "P3") (pin "3") (pinfunction "3_3") (pintype "passive"))
      (node (ref "Q10") (pin "2") (pinfunction "S_2") (pintype "passive"))
      (node (ref "Q11") (pin "2") (pinfunction "S_2") (pintype "passive"))
      (node (ref "Q4") (pin "2") (pinfunction "E_2") (pintype "passive"))
      (node (ref "Q5") (pin "2") (pinfunction "E_2") (pintype "passive"))
      (node (ref "Q6") (pin "2") (pinfunction "E_2") (pintype "passive"))
      (node (ref "Q7") (pin "2") (pinfunction "E_2") (pintype "passive"))
      (node (ref "Q8") (pin "2") (pinfunction "E_2") (pintype "passive"))
      (node (ref "Q9") (pin "2") (pinfunction "E_2") (pintype "passive"))
      (node (ref "R10") (pin "2") (pinfunction "2_2") (pintype "passive"))
      (node (ref "R12") (pin "2") (pinfunction "2_2") (pintype "passive"))
      (node (ref "R14") (pin "2") (pinfunction "2_2") (pintype "passive"))
      (node (ref "R20") (pin "2") (pinfunction "2_2") (pintype "passive"))
      (node (ref "R27") (pin "2") (pinfunction "2_2") (pintype "passive"))
      (node (ref "R28") (pin "1") (pinfunction "1_1") (pintype "passive"))
      (node (ref "R8") (pin "2") (pinfunction "2_2") (pintype "passive"))
      (node (ref "U1") (pin "1") (pinfunction "GND_1") (pintype "passive"))
      (node (ref "U2") (pin "1") (pinfunction "GND_1") (pintype "passive"))
      (node (ref "U3") (pin "18") (pinfunction "GND_18") (pintype "power_in"))
      (node (ref "U3") (pin "28") (pinfunction "GND_28") (pintype "power_in"))
      (node (ref "U3") (pin "39") (pinfunction "GND_39") (pintype "power_in"))
      (node (ref "U3") (pin "6") (pinfunction "GND_6") (pintype "power_in"))
      (node (ref "U4") (pin "1") (pinfunction "GND_1") (pintype "power_in"))
      (node (ref "U4") (pin "4") (pinfunction "V-_(CASE)_4") (pintype "power_in"))
      (node (ref "U5") (pin "1") (pinfunction "GND_1") (pintype "power_in"))
      (node (ref "U5") (pin "4") (pinfunction "V-_(CASE)_4") (pintype "power_in"))
      (node (ref "U6") (pin "4") (pinfunction "V-_4") (pintype "power_in"))
      (node (ref "U8") (pin "2") (pinfunction "CATHODE_2") (pintype "passive"))
      (node (ref "U8") (pin "4") (pinfunction "ENITIER_4") (pintype "passive"))
      (node (ref "U9") (pin "2") (pinfunction "CATHODE_2") (pintype "passive"))
      (node (ref "U9") (pin "4") (pinfunction "ENITIER_4") (pintype "passive"))
    )
    (net (code "36") (name "GND_BAT") (class "Default")
      (node (ref "U7") (pin "1") (pinfunction "ISEN_A_1") (pintype "passive"))
      (node (ref "U7") (pin "15") (pinfunction "ISEN_B_15") (pintype "passive"))
      (node (ref "U7") (pin "8") (pinfunction "GND_8") (pintype "power_in"))
    )
    (net (code "37") (name "LARM_MV") (class "Default")
      (node (ref "JP1") (pin "3") (pinfunction "3_3") (pintype "passive"))
      (node (ref "JP4") (pin "4") (pinfunction "4_4") (pintype "passive"))
      (node (ref "P2") (pin "1") (pinfunction "1_1") (pintype "passive"))
      (node (ref "U3") (pin "11") (pinfunction "PD2_(PCINT/26/INT0)_11") (pintype "bidirectional"))
      (node (ref "U3") (pin "34") (pinfunction "PA3_(ADC3/PCINT3)_34") (pintype "bidirectional"))
    )
    (net (code "38") (name "Net-(1-Pad1)") (class "Default")
      (node (ref "1") (pin "1") (pinfunction "1_1") (pintype "passive"))
      (node (ref "C10") (pin "2") (pinfunction "2_2") (pintype "passive"))
      (node (ref "C8") (pin "2") (pinfunction "2_2") (pintype "passive"))
    )
    (net (code "39") (name "Net-(C18-Pad1)") (class "Default")
      (node (ref "C18") (pin "1") (pinfunction "1_1") (pintype "passive"))
      (node (ref "R26") (pin "1") (pinfunction "1_1") (pintype "passive"))
    )
    (net (code "40") (name "Net-(C18-Pad2)") (class "Default")
      (node (ref "C18") (pin "2") (pinfunction "2_2") (pintype "passive"))
      (node (ref "MK1") (pin "1") (pinfunction "1_1") (pintype "passive"))
      (node (ref "R25") (pin "2") (pinfunction "2_2") (pintype "passive"))
    )
    (net (code "41") (name "Net-(D1-A)") (class "Default")
      (node (ref "D1") (pin "1") (pinfunction "A_1") (pintype "passive"))
      (node (ref "D2") (pin "1") (pinfunction "A_1") (pintype "passive"))
    )
    (net (code "42") (name "Net-(D1-K)") (class "Default")
      (node (ref "C6") (pin "2") (pinfunction "2_2") (pintype "passive"))
      (node (ref "D1") (pin "2") (pinfunction "K_2") (pintype "passive"))
      (node (ref "R14") (pin "1") (pinfunction "1_1") (pintype "passive"))
      (node (ref "U4") (pin "3") (pinfunction "IN-_3") (pintype "input"))
    )
    (net (code "43") (name "Net-(D2-K)") (class "Default")
      (node (ref "D2") (pin "2") (pinfunction "K_2") (pintype "passive"))
      (node (ref "U4") (pin "2") (pinfunction "IN+_2") (pintype "input"))
    )
    (net (code "44") (name "Net-(D3-A)") (class "Default")
      (node (ref "D3") (pin "1") (pinfunction "A_1") (pintype "passive"))
      (node (ref "J5") (pin "1") (pinfunction "1_1") (pintype "passive"))
      (node (ref "Q10") (pin "3") (pinfunction "D_3") (pintype "passive"))
    )
    (net (code "45") (name "Net-(D4-A)") (class "Default")
      (node (ref "D4") (pin "1") (pinfunction "A_1") (pintype "passive"))
      (node (ref "J6") (pin "1") (pinfunction "1_1") (pintype "passive"))
      (node (ref "Q11") (pin "3") (pinfunction "D_3") (pintype "passive"))
    )
    (net (code "46") (name "Net-(D9-K)") (class "Default")
      (node (ref "D9") (pin "2") (pinfunction "K_2") (pintype "passive"))
      (node (ref "R35") (pin "2") (pinfunction "2_2") (pintype "passive"))
    )
    (net (code "47") (name "Net-(D10-K)") (class "Default")
      (node (ref "D10") (pin "2") (pinfunction "K_2") (pintype "passive"))
      (node (ref "R36") (pin "2") (pinfunction "2_2") (pintype "passive"))
    )
    (net (code "48") (name "Net-(D11-K)") (class "Default")
      (node (ref "D11") (pin "2") (pinfunction "K_2") (pintype "passive"))
      (node (ref "R37") (pin "2") (pinfunction "2_2") (pintype "passive"))
    )
    (net (code "49") (name "Net-(D13-K)") (class "Default")
      (node (ref "D13") (pin "2") (pinfunction "K_2") (pintype "passive"))
      (node (ref "D16") (pin "2") (pinfunction "K_2") (pintype "passive"))
      (node (ref "D5") (pin "1") (pinfunction "A_1") (pintype "passive"))
      (node (ref "D6") (pin "1") (pinfunction "A_1") (pintype "passive"))
      (node (ref "M1") (pin "2") (pinfunction "2_2") (pintype "passive"))
      (node (ref "M2") (pin "2") (pinfunction "2_2") (pintype "passive"))
      (node (ref "R36") (pin "1") (pinfunction "1_1") (pintype "passive"))
      (node (ref "R38") (pin "1") (pinfunction "1_1") (pintype "passive"))
      (node (ref "U7") (pin "14") (pinfunction "OUT4_14") (pintype "output"))
      (node (ref "U7") (pin "3") (pinfunction "OUT2_3") (pintype "output"))
    )
    (net (code "50") (name "Net-(D14-K)") (class "Default")
      (node (ref "D14") (pin "2") (pinfunction "K_2") (pintype "passive"))
      (node (ref "D8") (pin "1") (pinfunction "A_1") (pintype "passive"))
      (node (ref "M1") (pin "1") (pinfunction "1_1") (pintype "passive"))
      (node (ref "R37") (pin "1") (pinfunction "1_1") (pintype "passive"))
      (node (ref "U7") (pin "13") (pinfunction "OUT3_13") (pintype "output"))
    )
    (net (code "51") (name "Net-(D15-K)") (class "Default")
      (node (ref "D15") (pin "2") (pinfunction "K_2") (pintype "passive"))
      (node (ref "D7") (pin "1") (pinfunction "A_1") (pintype "passive"))
      (node (ref "M2") (pin "1") (pinfunction "1_1") (pintype "passive"))
      (node (ref "R35") (pin "1") (pinfunction "1_1") (pintype "passive"))
      (node (ref "U7") (pin "2") (pinfunction "OUT1_2") (pintype "output"))
    )
    (net (code "52") (name "Net-(J1-CD{slash}DAT3)") (class "Default")
      (node (ref "J1") (pin "2") (pinfunction "CD/DAT3_2") (pintype "passive"))
      (node (ref "R11") (pin "1") (pinfunction "1_1") (pintype "passive"))
      (node (ref "R12") (pin "1") (pinfunction "1_1") (pintype "passive"))
    )
    (net (code "53") (name "Net-(J1-CLK)") (class "Default")
      (node (ref "J1") (pin "5") (pinfunction "CLK_5") (pintype "passive"))
      (node (ref "R6") (pin "1") (pinfunction "1_1") (pintype "passive"))
      (node (ref "R8") (pin "1") (pinfunction "1_1") (pintype "passive"))
    )
    (net (code "54") (name "Net-(J1-CMD)") (class "Default")
      (node (ref "J1") (pin "3") (pinfunction "CMD_3") (pintype "passive"))
      (node (ref "R10") (pin "1") (pinfunction "1_1") (pintype "passive"))
      (node (ref "R9") (pin "1") (pinfunction "1_1") (pintype "passive"))
    )
    (net (code "55") (name "Net-(J7-Pad1)") (class "Default")
      (node (ref "J7") (pin "1") (pinfunction "1_1") (pintype "passive"))
      (node (ref "R27") (pin "1") (pinfunction "1_1") (pintype "passive"))
    )
    (net (code "56") (name "Net-(P1-Pad1)") (class "Default")
      (node (ref "P1") (pin "1") (pinfunction "1_1") (pintype "passive"))
      (node (ref "R1") (pin "2") (pinfunction "2_2") (pintype "passive"))
    )
    (net (code "57") (name "Net-(P1-Pad3)") (class "Default")
      (node (ref "P1") (pin "3") (pinfunction "3_3") (pintype "passive"))
      (node (ref "R2") (pin "2") (pinfunction "2_2") (pintype "passive"))
    )
    (net (code "58") (name "Net-(P1-Pad5)") (class "Default")
      (node (ref "P1") (pin "5") (pinfunction "5_5") (pintype "passive"))
      (node (ref "R3") (pin "2") (pinfunction "2_2") (pintype "passive"))
    )
    (net (code "59") (name "Net-(P1-Pad9)") (class "Default")
      (node (ref "P1") (pin "9") (pinfunction "9_9") (pintype "passive"))
      (node (ref "R5") (pin "2") (pinfunction "2_2") (pintype "passive"))
    )
    (net (code "60") (name "Net-(Q1-B)") (class "Default")
      (node (ref "Q1") (pin "1") (pinfunction "B_1") (pintype "passive"))
      (node (ref "R16") (pin "2") (pinfunction "2_2") (pintype "passive"))
    )
    (net (code "61") (name "Net-(Q1-C)") (class "Default")
      (node (ref "J4") (pin "1") (pinfunction "1_1") (pintype "passive"))
      (node (ref "Q1") (pin "3") (pinfunction "C_3") (pintype "passive"))
      (node (ref "Q6") (pin "3") (pinfunction "C_3") (pintype "passive"))
    )
    (net (code "62") (name "Net-(Q2-B)") (class "Default")
      (node (ref "Q2") (pin "1") (pinfunction "B_1") (pintype "passive"))
      (node (ref "R15") (pin "2") (pinfunction "2_2") (pintype "passive"))
    )
    (net (code "63") (name "Net-(Q2-C)") (class "Default")
      (node (ref "J4") (pin "2") (pinfunction "2_2") (pintype "passive"))
      (node (ref "Q2") (pin "3") (pinfunction "C_3") (pintype "passive"))
      (node (ref "Q7") (pin "3") (pinfunction "C_3") (pintype "passive"))
    )
    (net (code "64") (name "Net-(Q3-G)") (class "Default")
      (node (ref "C8") (pin "1") (pinfunction "1_1") (pintype "passive"))
      (node (ref "C9") (pin "2") (pinfunction "2_2") (pintype "passive"))
      (node (ref "Q3") (pin "1") (pinfunction "G_1") (pintype "passive"))
    )
    (net (code "65") (name "Net-(Q3-S)") (class "Default")
      (node (ref "Q3") (pin "2") (pinfunction "S_2") (pintype "passive"))
      (node (ref "R20") (pin "1") (pinfunction "1_1") (pintype "passive"))
    )
    (net (code "66") (name "Net-(Q4-C)") (class "Default")
      (node (ref "Q4") (pin "3") (pinfunction "C_3") (pintype "passive"))
      (node (ref "R16") (pin "1") (pinfunction "1_1") (pintype "passive"))
    )
    (net (code "67") (name "Net-(Q5-C)") (class "Default")
      (node (ref "Q5") (pin "3") (pinfunction "C_3") (pintype "passive"))
      (node (ref "R15") (pin "1") (pinfunction "1_1") (pintype "passive"))
    )
    (net (code "68") (name "Net-(Q8-B)") (class "Default")
      (node (ref "Q8") (pin "1") (pinfunction "B_1") (pintype "passive"))
      (node (ref "R31") (pin "1") (pinfunction "1_1") (pintype "passive"))
    )
    (net (code "69") (name "Net-(Q9-B)") (class "Default")
      (node (ref "Q9") (pin "1") (pinfunction "B_1") (pintype "passive"))
      (node (ref "R32") (pin "1") (pinfunction "1_1") (pintype "passive"))
    )
    (net (code "70") (name "Net-(Q10-G)") (class "Default")
      (node (ref "Q10") (pin "1") (pinfunction "G_1") (pintype "passive"))
      (node (ref "Q8") (pin "3") (pinfunction "C_3") (pintype "passive"))
      (node (ref "R33") (pin "1") (pinfunction "1_1") (pintype "passive"))
    )
    (net (code "71") (name "Net-(Q11-G)") (class "Default")
      (node (ref "Q11") (pin "1") (pinfunction "G_1") (pintype "passive"))
      (node (ref "Q9") (pin "3") (pinfunction "C_3") (pintype "passive"))
      (node (ref "R34") (pin "1") (pinfunction "1_1") (pintype "passive"))
    )
    (net (code "72") (name "Net-(R29-Pad2)") (class "Default")
      (node (ref "R29") (pin "2") (pinfunction "2_2") (pintype "passive"))
      (node (ref "R30") (pin "1") (pinfunction "1_1") (pintype "passive"))
    )
    (net (code "73") (name "Net-(U3-XTAL1)") (class "Default")
      (node (ref "C17") (pin "2") (pinfunction "2_2") (pintype "passive"))
      (node (ref "U3") (pin "8") (pinfunction "XTAL1_8") (pintype "passive"))
      (node (ref "X1") (pin "1") (pinfunction "OSC1_1") (pintype "passive"))
    )
    (net (code "74") (name "Net-(U3-XTAL2)") (class "Default")
      (node (ref "C14") (pin "2") (pinfunction "2_2") (pintype "passive"))
      (node (ref "U3") (pin "7") (pinfunction "XTAL2_7") (pintype "passive"))
      (node (ref "X1") (pin "2") (pinfunction "OSC2_2") (pintype "passive"))
    )
    (net (code "75") (name "Net-(U5-IN+)") (class "Default")
      (node (ref "J7") (pin "2") (pinfunction "2_2") (pintype "passive"))
      (node (ref "U5") (pin "2") (pinfunction "IN+_2") (pintype "input"))
    )
    (net (code "76") (name "Net-(U6A-IN+)") (class "Default")
      (node (ref "R28") (pin "2") (pinfunction "2_2") (pintype "passive"))
      (node (ref "R29") (pin "1") (pinfunction "1_1") (pintype "passive"))
      (node (ref "U6") (pin "3") (pinfunction "IN+_3") (pintype "input"))
    )
    (net (code "77") (name "Net-(U6A-IN-)") (class "Default")
      (node (ref "R23") (pin "1") (pinfunction "1_1") (pintype "passive"))
      (node (ref "R26") (pin "2") (pinfunction "2_2") (pintype "passive"))
      (node (ref "U6") (pin "2") (pinfunction "IN-_2") (pintype "input"))
    )
    (net (code "78") (name "Net-(U8-ANODE)") (class "Default")
      (node (ref "R42") (pin "1") (pinfunction "1_1") (pintype "passive"))
      (node (ref "U8") (pin "1") (pinfunction "ANODE_1") (pintype "passive"))
    )
    (net (code "79") (name "Net-(U9-ANODE)") (class "Default")
      (node (ref "2") (pin "1") (pinfunction "1_1") (pintype "passive"))
      (node (ref "U9") (pin "1") (pinfunction "ANODE_1") (pintype "passive"))
    )
    (net (code "80") (name "RARM_MV") (class "Default")
      (node (ref "JP1") (pin "4") (pinfunction "4_4") (pintype "passive"))
      (node (ref "JP4") (pin "5") (pinfunction "5_5") (pintype "passive"))
      (node (ref "P3") (pin "1") (pinfunction "1_1") (pintype "passive"))
      (node (ref "U3") (pin "12") (pinfunction "PD3_(PCINT/27/INT1)_12") (pintype "bidirectional"))
      (node (ref "U3") (pin "33") (pinfunction "PA4_(ADC4/PCINT4)_33") (pintype "bidirectional"))
    )
    (net (code "81") (name "V3") (class "Default")
      (node (ref "C1") (pin "1") (pinfunction "1_1") (pintype "passive"))
      (node (ref "C2") (pin "2") (pinfunction "2_2") (pintype "passive"))
      (node (ref "J1") (pin "4") (pinfunction "VDD_4") (pintype "passive"))
      (node (ref "JP2") (pin "4") (pinfunction "4_4") (pintype "passive"))
      (node (ref "U1") (pin "2") (pinfunction "OUT_2") (pintype "passive"))
    )
    (net (code "82") (name "VBAT") (class "Default")
      (node (ref "B1") (pin "2") (pintype "passive"))
      (node (ref "B1") (pin "5") (pintype "passive"))
      (node (ref "JP2") (pin "8") (pinfunction "8_8") (pintype "passive"))
    )
    (net (code "83") (name "VBATT") (class "Default")
      (node (ref "C11") (pin "2") (pinfunction "2_2") (pintype "passive"))
      (node (ref "C23") (pin "1") (pinfunction "1_1") (pintype "passive"))
      (node (ref "C25") (pin "1") (pinfunction "1_1") (pintype "passive"))
      (node (ref "D10") (pin "1") (pinfunction "A_1") (pintype "passive"))
      (node (ref "D11") (pin "1") (pinfunction "A_1") (pintype "passive"))
      (node (ref "D12") (pin "1") (pinfunction "A_1") (pintype "passive"))
      (node (ref "D3") (pin "2") (pinfunction "K_2") (pintype "passive"))
      (node (ref "D4") (pin "2") (pinfunction "K_2") (pintype "passive"))
      (node (ref "D5") (pin "2") (pinfunction "K_2") (pintype "passive"))
      (node (ref "D6") (pin "2") (pinfunction "K_2") (pintype "passive"))
      (node (ref "D7") (pin "2") (pinfunction "K_2") (pintype "passive"))
      (node (ref "D8") (pin "2") (pinfunction "K_2") (pintype "passive"))
      (node (ref "D9") (pin "1") (pinfunction "A_1") (pintype "passive"))
      (node (ref "J5") (pin "2") (pinfunction "2_2") (pintype "passive"))
      (node (ref "J6") (pin "2") (pinfunction "2_2") (pintype "passive"))
      (node (ref "U1") (pin "3") (pinfunction "IN_3") (pintype "passive"))
      (node (ref "U2") (pin "3") (pinfunction "IN_3") (pintype "passive"))
      (node (ref "U4") (pin "8") (pinfunction "V+_8") (pintype "power_in"))
      (node (ref "U7") (pin "4") (pinfunction "VS_4") (pintype "power_in"))
    )
    (net (code "84") (name "VCC") (class "Default")
      (node (ref "2") (pin "2") (pinfunction "2_2") (pintype "passive"))
      (node (ref "C12") (pin "2") (pinfunction "2_2") (pintype "passive"))
      (node (ref "C13") (pin "2") (pinfunction "2_2") (pintype "passive"))
      (node (ref "C15") (pin "1") (pinfunction "1_1") (pintype "passive"))
      (node (ref "C16") (pin "2") (pinfunction "2_2") (pintype "passive"))
      (node (ref "C19") (pin "2") (pinfunction "2_2") (pintype "passive"))
      (node (ref "C21") (pin "2") (pinfunction "2_2") (pintype "passive"))
      (node (ref "C24") (pin "1") (pinfunction "1_1") (pintype "passive"))
      (node (ref "C3") (pin "1") (pinfunction "1_1") (pintype "passive"))
      (node (ref "C4") (pin "2") (pinfunction "2_2") (pintype "passive"))
      (node (ref "J3") (pin "2") (pinfunction "2_2") (pintype "passive"))
      (node (ref "JP2") (pin "2") (pinfunction "2_2") (pintype "passive"))
      (node (ref "JP2") (pin "5") (pinfunction "5_5") (pintype "passive"))
      (node (ref "P2") (pin "2") (pinfunction "2_2") (pintype "passive"))
      (node (ref "P3") (pin "2") (pinfunction "2_2") (pintype "passive"))
      (node (ref "Q1") (pin "2") (pinfunction "E_2") (pintype "passive"))
      (node (ref "Q2") (pin "2") (pinfunction "E_2") (pintype "passive"))
      (node (ref "Q3") (pin "3") (pinfunction "D_3") (pintype "passive"))
      (node (ref "R1") (pin "1") (pinfunction "1_1") (pintype "passive"))
      (node (ref "R13") (pin "1") (pinfunction "1_1") (pintype "passive"))
      (node (ref "R17") (pin "1") (pinfunction "1_1") (pintype "passive"))
      (node (ref "R2") (pin "1") (pinfunction "1_1") (pintype "passive"))
      (node (ref "R24") (pin "1") (pinfunction "1_1") (pintype "passive"))
      (node (ref "R25") (pin "1") (pinfunction "1_1") (pintype "passive"))
      (node (ref "R3") (pin "1") (pinfunction "1_1") (pintype "passive"))
      (node (ref "R30") (pin "2") (pinfunction "2_2") (pintype "passive"))
      (node (ref "R4") (pin "1") (pinfunction "1_1") (pintype "passive"))
      (node (ref "R42") (pin "2") (pinfunction "2_2") (pintype "passive"))
      (node (ref "R43") (pin "2") (pinfunction "2_2") (pintype "passive"))
      (node (ref "R44") (pin "2") (pinfunction "2_2") (pintype "passive"))
      (node (ref "R5") (pin "1") (pinfunction "1_1") (pintype "passive"))
      (node (ref "R7") (pin "1") (pinfunction "1_1") (pintype "passive"))
      (node (ref "U2") (pin "2") (pinfunction "OUT_2") (pintype "passive"))
      (node (ref "U3") (pin "17") (pinfunction "VCC_17") (pintype "power_in"))
      (node (ref "U3") (pin "27") (pinfunction "AVCC_27") (pintype "power_in"))
      (node (ref "U3") (pin "38") (pinfunction "VCC_38") (pintype "power_in"))
      (node (ref "U3") (pin "5") (pinfunction "VCC_5") (pintype "power_in"))
      (node (ref "U5") (pin "3") (pinfunction "IN-_3") (pintype "input"))
      (node (ref "U6") (pin "8") (pinfunction "V+_8") (pintype "power_in"))
      (node (ref "U7") (pin "9") (pinfunction "VSS_9") (pintype "power_in"))
    )
    (net (code "85") (name "Vb") (class "Default")
      (node (ref "B1") (pin "3") (pintype "passive"))
      (node (ref "B1") (pin "4") (pintype "passive"))
      (node (ref "BAT1") (pin "2") (pinfunction "2_2") (pintype "passive"))
    )
    (net (code "86") (name "unconnected-(B1-Pad1)") (class "Default")
      (node (ref "B1") (pin "1") (pintype "passive+no_connect"))
    )
    (net (code "87") (name "unconnected-(B1-Pad6)") (class "Default")
      (node (ref "B1") (pin "6") (pintype "passive+no_connect"))
    )
    (net (code "88") (name "unconnected-(D12-K-Pad2)") (class "Default")
      (node (ref "D12") (pin "2") (pinfunction "K_2") (pintype "passive"))
    )
    (net (code "89") (name "unconnected-(J1-DAT1-Pad8)") (class "Default")
      (node (ref "J1") (pin "8") (pinfunction "DAT1_8") (pintype "passive+no_connect"))
    )
    (net (code "90") (name "unconnected-(J1-DAT2-Pad1)") (class "Default")
      (node (ref "J1") (pin "1") (pinfunction "DAT2_1") (pintype "passive+no_connect"))
    )
    (net (code "91") (name "unconnected-(J1-Pad9)") (class "Default")
      (node (ref "J1") (pin "9") (pinfunction "9_9") (pintype "passive+no_connect"))
    )
    (net (code "92") (name "unconnected-(J1-Pad10)") (class "Default")
      (node (ref "J1") (pin "10") (pinfunction "10_10") (pintype "passive+no_connect"))
    )
    (net (code "93") (name "unconnected-(J1-Pad11)") (class "Default")
      (node (ref "J1") (pin "11") (pinfunction "11_11") (pintype "passive+no_connect"))
    )
    (net (code "94") (name "unconnected-(J1-Pad12)") (class "Default")
      (node (ref "J1") (pin "12") (pinfunction "12_12") (pintype "passive+no_connect"))
    )
    (net (code "95") (name "unconnected-(J2-Pad1)") (class "Default")
      (node (ref "J2") (pin "1") (pinfunction "1_1") (pintype "passive+no_connect"))
    )
    (net (code "96") (name "unconnected-(J2-Pad6)") (class "Default")
      (node (ref "J2") (pin "6") (pinfunction "6_6") (pintype "passive+no_connect"))
    )
    (net (code "97") (name "unconnected-(JP1-Pad9)") (class "Default")
      (node (ref "JP1") (pin "9") (pinfunction "9_9") (pintype "passive"))
    )
    (net (code "98") (name "unconnected-(JP1-Pad10)") (class "Default")
      (node (ref "JP1") (pin "10") (pinfunction "10_10") (pintype "passive"))
    )
    (net (code "99") (name "unconnected-(JP2-Pad1)") (class "Default")
      (node (ref "JP2") (pin "1") (pinfunction "1_1") (pintype "passive+no_connect"))
    )
    (net (code "100") (name "unconnected-(Q4-B-Pad1)") (class "Default")
      (node (ref "Q4") (pin "1") (pinfunction "B_1") (pintype "passive"))
    )
    (net (code "101") (name "unconnected-(Q5-B-Pad1)") (class "Default")
      (node (ref "Q5") (pin "1") (pinfunction "B_1") (pintype "passive"))
    )
    (net (code "102") (name "unconnected-(Q6-B-Pad1)") (class "Default")
      (node (ref "Q6") (pin "1") (pinfunction "B_1") (pintype "passive"))
    )
    (net (code "103") (name "unconnected-(Q7-B-Pad1)") (class "Default")
      (node (ref "Q7") (pin "1") (pinfunction "B_1") (pintype "passive"))
    )
    (net (code "104") (name "unconnected-(R18-Pad2)") (class "Default")
      (node (ref "R18") (pin "2") (pinfunction "2_2") (pintype "passive"))
    )
    (net (code "105") (name "unconnected-(R19-Pad2)") (class "Default")
      (node (ref "R19") (pin "2") (pinfunction "2_2") (pintype "passive"))
    )
    (net (code "106") (name "unconnected-(R21-Pad1)") (class "Default")
      (node (ref "R21") (pin "1") (pinfunction "1_1") (pintype "passive"))
    )
    (net (code "107") (name "unconnected-(R21-Pad2)") (class "Default")
      (node (ref "R21") (pin "2") (pinfunction "2_2") (pintype "passive"))
    )
    (net (code "108") (name "unconnected-(R22-Pad1)") (class "Default")
      (node (ref "R22") (pin "1") (pinfunction "1_1") (pintype "passive"))
    )
    (net (code "109") (name "unconnected-(R22-Pad2)") (class "Default")
      (node (ref "R22") (pin "2") (pinfunction "2_2") (pintype "passive"))
    )
    (net (code "110") (name "unconnected-(R38-Pad2)") (class "Default")
      (node (ref "R38") (pin "2") (pinfunction "2_2") (pintype "passive"))
    )
    (net (code "111") (name "unconnected-(U4-BAL-Pad5)") (class "Default")
      (node (ref "U4") (pin "5") (pinfunction "BAL_5") (pintype "passive"))
    )
    (net (code "112") (name "unconnected-(U4-BAL{slash}STB-Pad6)") (class "Default")
      (node (ref "U4") (pin "6") (pinfunction "BAL/STB_6") (pintype "passive"))
    )
    (net (code "113") (name "unconnected-(U5-BAL-Pad5)") (class "Default")
      (node (ref "U5") (pin "5") (pinfunction "BAL_5") (pintype "passive"))
    )
    (net (code "114") (name "unconnected-(U5-BAL{slash}STB-Pad6)") (class "Default")
      (node (ref "U5") (pin "6") (pinfunction "BAL/STB_6") (pintype "passive"))
    )
    (net (code "115") (name "unconnected-(U5-V+-Pad8)") (class "Default")
      (node (ref "U5") (pin "8") (pinfunction "V+_8") (pintype "power_in"))
    )
  )
)
